# Led_array.net
KiCad netlist of a schematic drawn in EAGLE
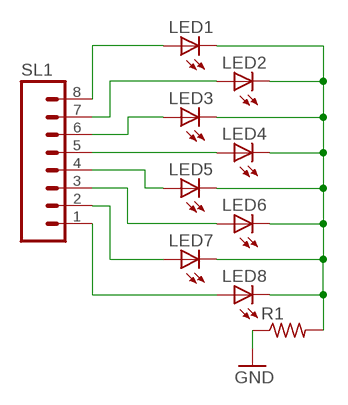
[diagram p0: schematic, sheet 1]

(export (version "E")
  (design (tool "Eeschema 10.0.6"))
  (components
    (comp (ref "LED1")
      (value "LED3MM")
      (footprint "eagle-import:LED3MM")
      (libsource (lib "eagle-import") (part "LED3MM"))
    )
    (comp (ref "LED2")
      (value "LED3MM")
      (footprint "eagle-import:LED3MM")
      (libsource (lib "eagle-import") (part "LED3MM"))
    )
    (comp (ref "LED3")
      (value "LED3MM")
      (footprint "eagle-import:LED3MM")
      (libsource (lib "eagle-import") (part "LED3MM"))
    )
    (comp (ref "LED4")
      (value "LED3MM")
      (footprint "eagle-import:LED3MM")
      (libsource (lib "eagle-import") (part "LED3MM"))
    )
    (comp (ref "LED5")
      (value "LED3MM")
      (footprint "eagle-import:LED3MM")
      (libsource (lib "eagle-import") (part "LED3MM"))
    )
    (comp (ref "LED6")
      (value "LED3MM")
      (footprint "eagle-import:LED3MM")
      (libsource (lib "eagle-import") (part "LED3MM"))
    )
    (comp (ref "LED7")
      (value "LED3MM")
      (footprint "eagle-import:LED3MM")
      (libsource (lib "eagle-import") (part "LED3MM"))
    )
    (comp (ref "LED8")
      (value "LED3MM")
      (footprint "eagle-import:LED3MM")
      (libsource (lib "eagle-import") (part "LED3MM"))
    )
    (comp (ref "R1")
      (value "R-US_0204/7")
      (footprint "eagle-import:0204_7")
      (libsource (lib "eagle-import") (part "R-US_0204/7"))
    )
    (comp (ref "SL1")
      (value "M08")
      (footprint "eagle-import:08P")
      (libsource (lib "eagle-import") (part "M08"))
    )
  )
  (nets
    (net (code "1") (name "GND") (class "Default")
      (node (ref "R1") (pin "1") (pinfunction "1_1") (pintype "passive"))
    )
    (net (code "2") (name "Net-(LED1-C)") (class "Default")
      (node (ref "LED1") (pin "K") (pinfunction "C_K") (pintype "passive"))
      (node (ref "LED2") (pin "K") (pinfunction "C_K") (pintype "passive"))
      (node (ref "LED3") (pin "K") (pinfunction "C_K") (pintype "passive"))
      (node (ref "LED4") (pin "K") (pinfunction "C_K") (pintype "passive"))
      (node (ref "LED5") (pin "K") (pinfunction "C_K") (pintype "passive"))
      (node (ref "LED6") (pin "K") (pinfunction "C_K") (pintype "passive"))
      (node (ref "LED7") (pin "K") (pinfunction "C_K") (pintype "passive"))
      (node (ref "LED8") (pin "K") (pinfunction "C_K") (pintype "passive"))
      (node (ref "R1") (pin "2") (pinfunction "2_2") (pintype "passive"))
    )
    (net (code "3") (name "Net-(LED1-PadA)") (class "Default")
      (node (ref "LED1") (pin "A") (pinfunction "A_A") (pintype "passive"))
      (node (ref "SL1") (pin "8") (pinfunction "8_8") (pintype "passive"))
    )
    (net (code "4") (name "Net-(LED2-PadA)") (class "Default")
      (node (ref "LED2") (pin "A") (pinfunction "A_A") (pintype "passive"))
      (node (ref "SL1") (pin "7") (pinfunction "7_7") (pintype "passive"))
    )
    (net (code "5") (name "Net-(LED3-PadA)") (class "Default")
      (node (ref "LED3") (pin "A") (pinfunction "A_A") (pintype "passive"))
      (node (ref "SL1") (pin "6") (pinfunction "6_6") (pintype "passive"))
    )
    (net (code "6") (name "Net-(LED4-PadA)") (class "Default")
      (node (ref "LED4") (pin "A") (pinfunction "A_A") (pintype "passive"))
      (node (ref "SL1") (pin "5") (pinfunction "5_5") (pintype "passive"))
    )
    (net (code "7") (name "Net-(LED5-PadA)") (class "Default")
      (node (ref "LED5") (pin "A") (pinfunction "A_A") (pintype "passive"))
      (node (ref "SL1") (pin "4") (pinfunction "4_4") (pintype "passive"))
    )
    (net (code "8") (name "Net-(LED6-PadA)") (class "Default")
      (node (ref "LED6") (pin "A") (pinfunction "A_A") (pintype "passive"))
      (node (ref "SL1") (pin "3") (pinfunction "3_3") (pintype "passive"))
    )
    (net (code "9") (name "Net-(LED7-PadA)") (class "Default")
      (node (ref "LED7") (pin "A") (pinfunction "A_A") (pintype "passive"))
      (node (ref "SL1") (pin "2") (pinfunction "2_2") (pintype "passive"))
    )
    (net (code "10") (name "Net-(LED8-PadA)") (class "Default")
      (node (ref "LED8") (pin "A") (pinfunction "A_A") (pintype "passive"))
      (node (ref "SL1") (pin "1") (pinfunction "1_1") (pintype "passive"))
    )
  )
)
